# V2_1_1_AC_Power_Switch.net
KiCad netlist of a schematic drawn in EasyEDA Pro
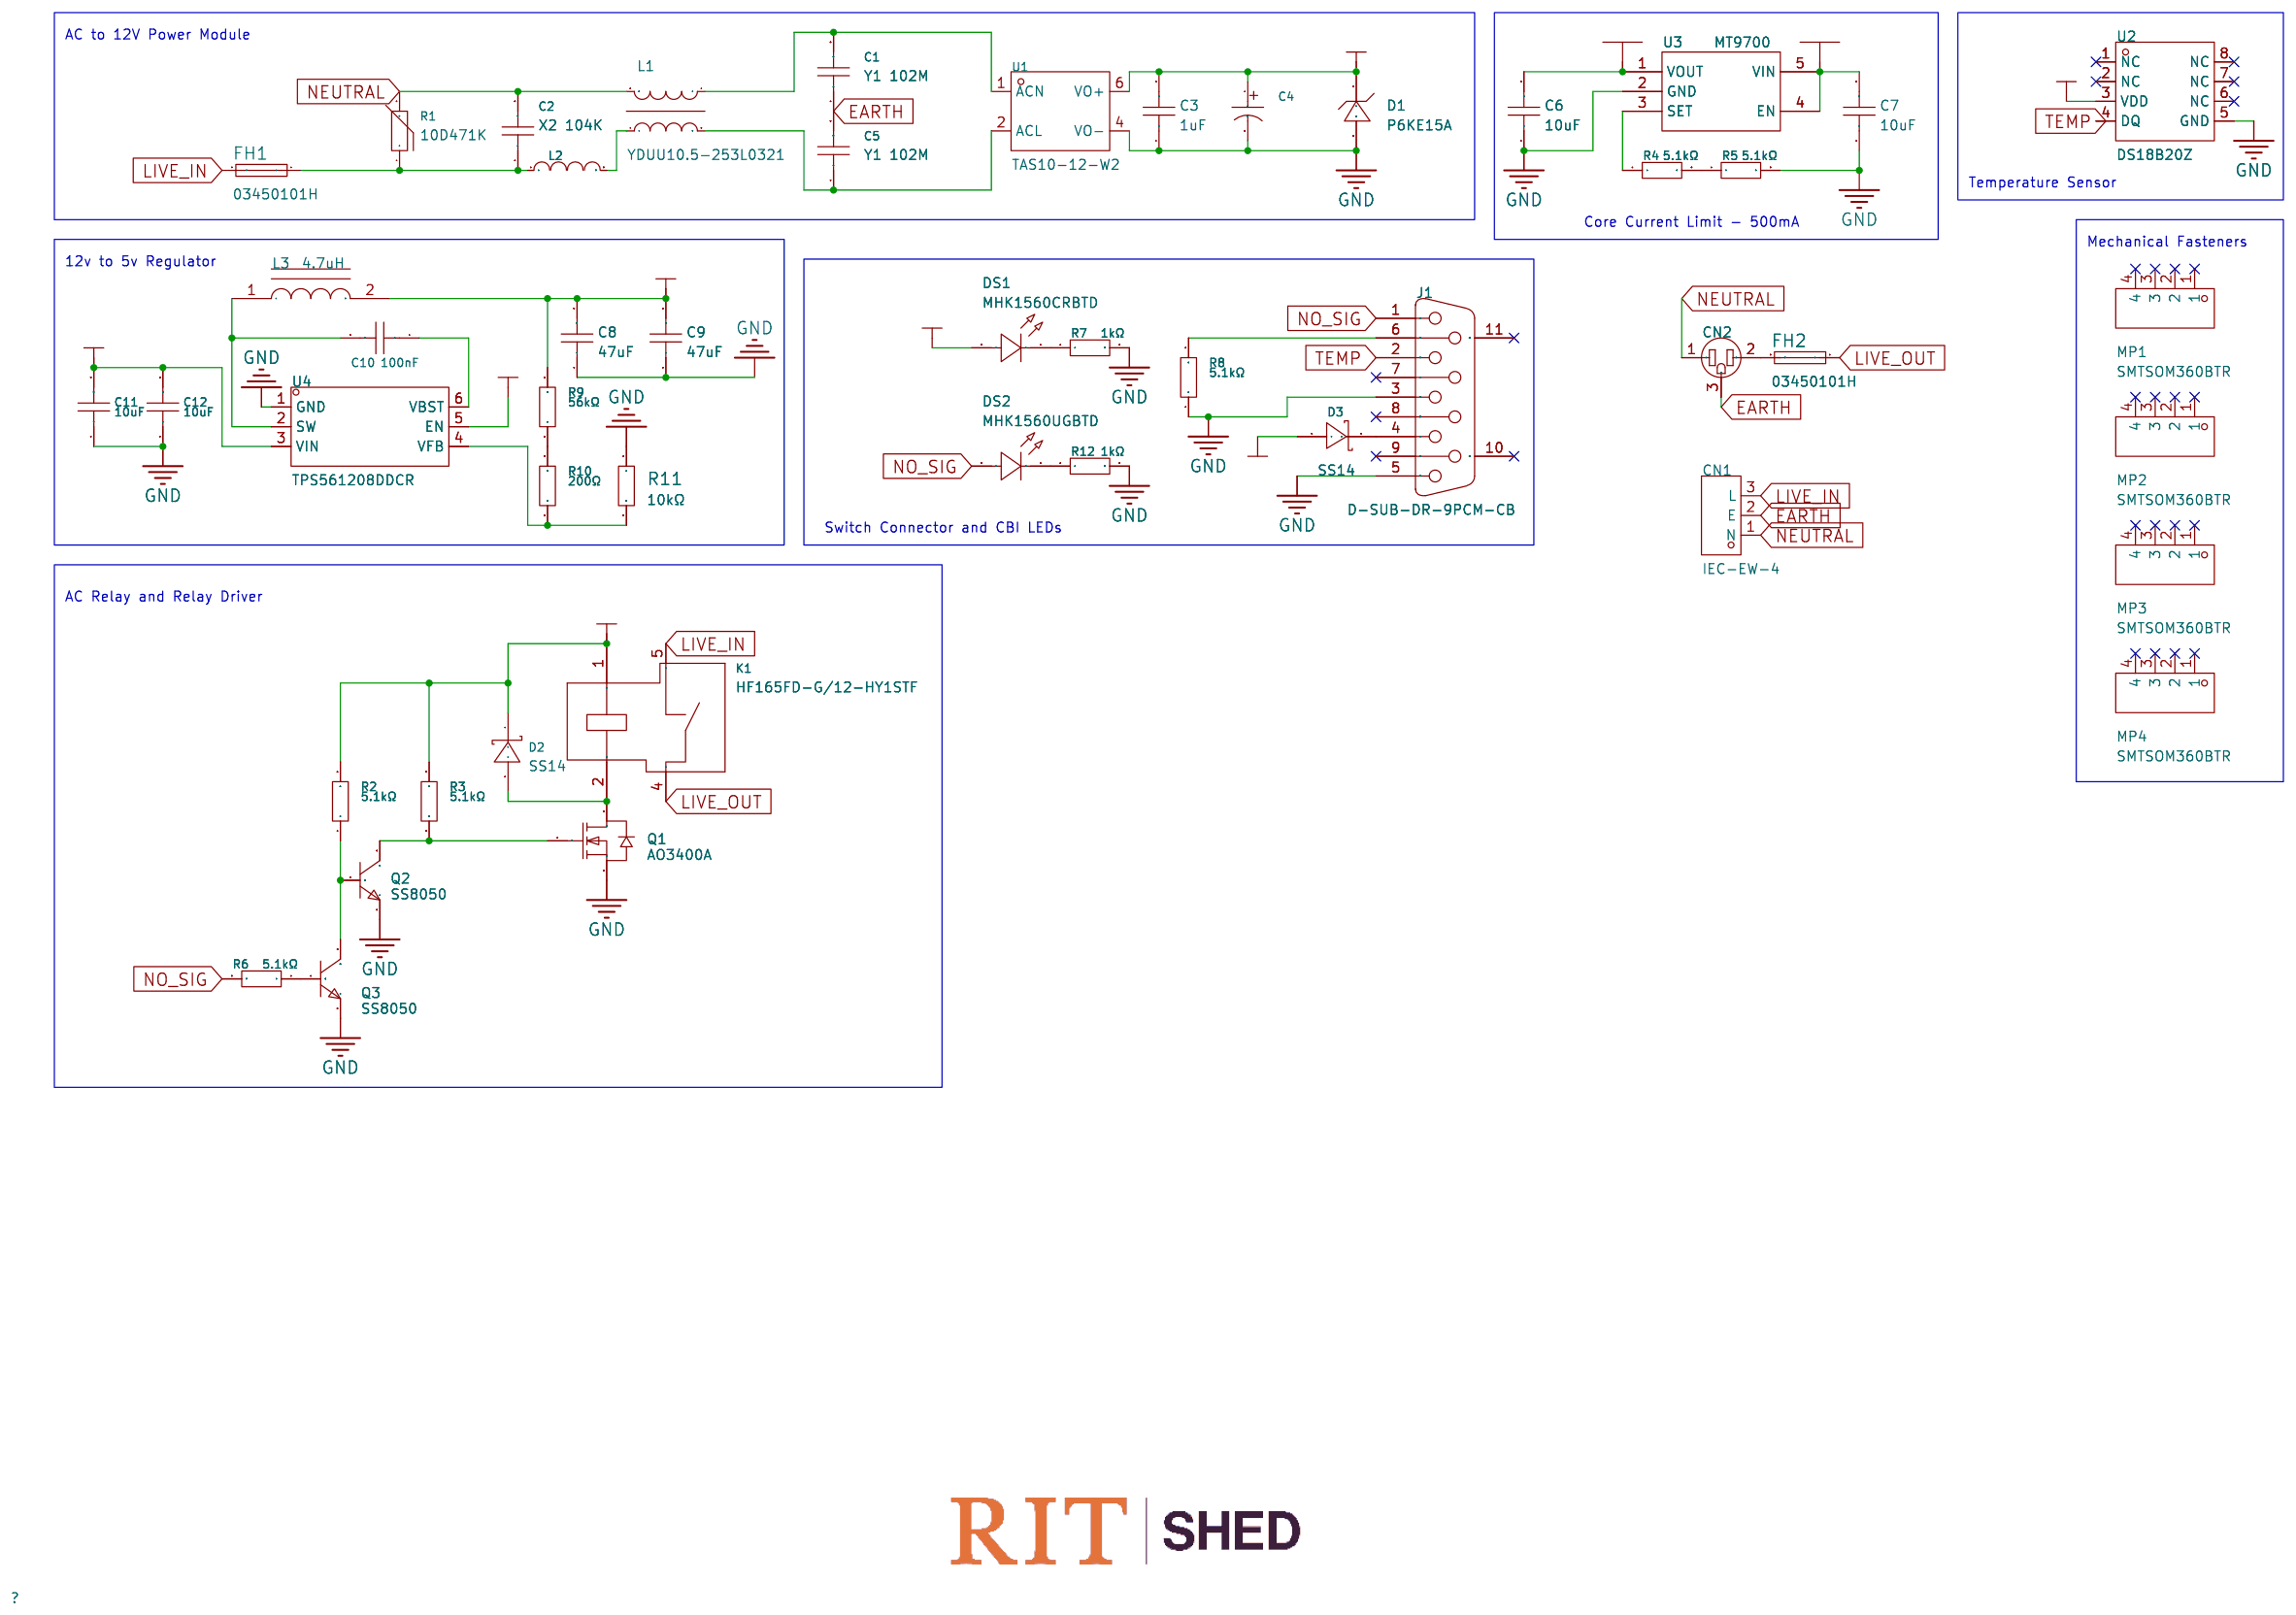
[diagram p0: schematic sheet]

(export (version "E")
  (design (tool "Eeschema 10.0.6"))
  (components
    (comp (ref "C1")
      (value "1nF")
      (footprint "easyedapro:CAP-TH_L8.5-W5.0-P10.00-D0.6")
      (fields
        (field (name "Manufacturer Part") "VY1102M31Y5UC63V0")
        (field (name "Manufacturer") "VISHAY(威世)")
      )
      (libsource (lib "easyedapro") (part "VY1102M31Y5UC63V0"))
    )
    (comp (ref "C2")
      (value "100nF")
      (footprint "easyedapro:CAP-TH_L10.0-W5.0-P7.50-D0.6")
      (fields (field (name "Manufacturer Part") "PX104K2C0702") (field (name "Manufacturer") "KYET(科雅)"))
      (libsource (lib "easyedapro") (part "PX104K2C0702"))
    )
    (comp (ref "C3")
      (value "1uF")
      (footprint "easyedapro:C1206")
      (fields
        (field (name "Manufacturer Part") "CL31B105KBHNNNE")
        (field (name "Manufacturer") "SAMSUNG(三星)")
      )
      (libsource (lib "easyedapro") (part "CL31B105KBHNNNE"))
    )
    (comp (ref "C4")
      (value "220uF")
      (footprint "easyedapro:CAP-TH_BD6.3-P2.50-D1.0-FD")
      (fields
        (field (name "Manufacturer Part") "KM227M025E11RR0VH2FP0")
        (field (name "Manufacturer") "CX(承兴)")
      )
      (libsource (lib "easyedapro") (part "220uF 25V_C12450"))
    )
    (comp (ref "C5")
      (value "1nF")
      (footprint "easyedapro:CAP-TH_L8.5-W5.0-P10.00-D0.6")
      (fields
        (field (name "Manufacturer Part") "VY1102M31Y5UC63V0")
        (field (name "Manufacturer") "VISHAY(威世)")
      )
      (libsource (lib "easyedapro") (part "VY1102M31Y5UC63V0"))
    )
    (comp (ref "C6")
      (value "10uF")
      (footprint "easyedapro:C0603")
      (fields
        (field (name "Manufacturer Part") "CL10A106MA8NRNC")
        (field (name "Manufacturer") "SAMSUNG(三星)")
      )
      (libsource (lib "easyedapro") (part "CL10A106MA8NRNC"))
    )
    (comp (ref "C7")
      (value "10uF")
      (footprint "easyedapro:C0603")
      (fields
        (field (name "Manufacturer Part") "CL10A106MA8NRNC")
        (field (name "Manufacturer") "SAMSUNG(三星)")
      )
      (libsource (lib "easyedapro") (part "CL10A106MA8NRNC"))
    )
    (comp (ref "C8")
      (value "47uF")
      (footprint "easyedapro:C1206")
      (fields
        (field (name "Manufacturer Part") "CL31A476MPHNNNE")
        (field (name "Manufacturer") "SAMSUNG(三星)")
      )
      (libsource (lib "easyedapro") (part "CL31A476MPHNNNE"))
    )
    (comp (ref "C9")
      (value "47uF")
      (footprint "easyedapro:C1206")
      (fields
        (field (name "Manufacturer Part") "CL31A476MPHNNNE")
        (field (name "Manufacturer") "SAMSUNG(三星)")
      )
      (libsource (lib "easyedapro") (part "CL31A476MPHNNNE"))
    )
    (comp (ref "C10")
      (value "100nF")
      (footprint "easyedapro:C0603")
      (fields
        (field (name "Manufacturer Part") "CC0603KRX7R9BB104")
        (field (name "Manufacturer") "YAGEO(国巨)")
      )
      (libsource (lib "easyedapro") (part "CC0603KRX7R9BB104"))
    )
    (comp (ref "C11")
      (value "10uF")
      (footprint "easyedapro:C0603")
      (fields
        (field (name "Manufacturer Part") "CL10A106MA8NRNC")
        (field (name "Manufacturer") "SAMSUNG(三星)")
      )
      (libsource (lib "easyedapro") (part "CL10A106MA8NRNC"))
    )
    (comp (ref "C12")
      (value "10uF")
      (footprint "easyedapro:C0603")
      (fields
        (field (name "Manufacturer Part") "CL10A106MA8NRNC")
        (field (name "Manufacturer") "SAMSUNG(三星)")
      )
      (libsource (lib "easyedapro") (part "CL10A106MA8NRNC"))
    )
    (comp (ref "CN1")
      (value "IEC-EW-4")
      (footprint "easyedapro:CONN-TH_IEC-EW-4")
      (fields (field (name "Manufacturer") "ADAM TECH"))
      (libsource (lib "easyedapro") (part "IEC-EW-4"))
    )
    (comp (ref "CN2")
      (value "~")
      (footprint "easyedapro:739W-X2/32")
      (libsource (lib "easyedapro") (part "739W-X2/32"))
    )
    (comp (ref "D1")
      (value "P6KE15A")
      (footprint "easyedapro:DO-15_BD3.1-L6.7-P10.70-D0.9-RD")
      (fields (field (name "Manufacturer") "PINGWEI(平伟)"))
      (libsource (lib "easyedapro") (part "P6KE15A_C432720"))
    )
    (comp (ref "D2")
      (value "SS14")
      (footprint "easyedapro:SMA_L4.2-W2.6-LS5.3-RD")
      (fields (field (name "Manufacturer") "MDD"))
      (libsource (lib "easyedapro") (part "SS14"))
    )
    (comp (ref "D3")
      (value "SS14")
      (footprint "easyedapro:SMA_L4.2-W2.6-LS5.3-RD")
      (fields (field (name "Manufacturer") "MDD"))
      (libsource (lib "easyedapro") (part "SS14"))
    )
    (comp (ref "DS1")
      (value "MHK1560CRBTD")
      (footprint "easyedapro:LED-TH_MHK1560UGBTD")
      (fields (field (name "Manufacturer") "MEIHUA(美华)"))
      (libsource (lib "easyedapro") (part "MHK1560CGBTD"))
    )
    (comp (ref "DS2")
      (value "MHK1560UGBTD")
      (footprint "easyedapro:LED-TH_MHK1560UGBTD")
      (fields (field (name "Manufacturer") "MEIHUA(美华)"))
      (libsource (lib "easyedapro") (part "MHK1560UGBTD"))
    )
    (comp (ref "FH1")
      (value "03450101H")
      (footprint "easyedapro:03450101H")
      (description "Fuseholder Type:- Fuse Type:- Fuse Size:-")
      (fields (field (name "Manufacturer") "Littelfuse(美国力特)"))
      (libsource (lib "easyedapro") (part "03450101H"))
    )
    (comp (ref "FH2")
      (value "03450101H")
      (footprint "easyedapro:03450101H")
      (description "Fuseholder Type:- Fuse Type:- Fuse Size:-")
      (fields (field (name "Manufacturer") "Littelfuse(美国力特)"))
      (libsource (lib "easyedapro") (part "03450101H"))
    )
    (comp (ref "J1")
      (value "D-SUB-DR-9PCM-CB")
      (footprint "easyedapro:DB9-TH_ID09S33E4GV00LF")
      (fields (field (name "Manufacturer") "XUNPU(讯普)"))
      (libsource (lib "easyedapro") (part "D-SUB-DR-9PCM-CB"))
    )
    (comp (ref "K1")
      (value "HF165FD-G/12-HY1STF")
      (footprint "easyedapro:RELAY-TH_HF165FD-G-12-HY1STF")
      (fields (field (name "Manufacturer") "HF(宏发)"))
      (libsource (lib "easyedapro") (part "HF165FD-G/12-HY1STF"))
    )
    (comp (ref "L1")
      (value "YDUU10.5-253L0321")
      (footprint "easyedapro:IND-TH_4P-L19.0-W17.0")
      (description "Number of Lines:2 Withstanding Voltage:1.5kV@AC Inductance @ Frequency:25mH@1KHz")
      (fields (field (name "Manufacturer") "YJYCOIN(益嘉源)"))
      (libsource (lib "easyedapro") (part "YDUU10.5-253L0321"))
    )
    (comp (ref "L2")
      (value "560uH")
      (footprint "easyedapro:IND-TH_BD9.0-P5.00-D0.7")
      (description "Inductance: Tolerance:±10% Tolerance:±10% Rated Current: DC Resistance (DCR): Type:工字电感")
      (fields (field (name "Manufacturer Part") "PK0810-561KB") (field (name "Manufacturer") "SXN(顺翔诺)"))
      (libsource (lib "easyedapro") (part "PK0810-561KB"))
    )
    (comp (ref "L3")
      (value "4.7uH")
      (footprint "easyedapro:IND-SMD_L4.4-W4.2")
      (fields (field (name "Manufacturer Part") "BCIHP0420SC-4R7M") (field (name "Manufacturer") "BC(台湾诚阳)"))
      (libsource (lib "easyedapro") (part "BCIHP0420SC-4R7M_C2921168"))
    )
    (comp (ref "MP1")
      (value "SMTSOM360BTR")
      (footprint "easyedapro:SMD_BD5.6-D4.1")
      (fields (field (name "Manufacturer") "YIYUAN(怡远)"))
      (libsource (lib "easyedapro") (part "SMTSOM360BTR"))
    )
    (comp (ref "MP2")
      (value "SMTSOM360BTR")
      (footprint "easyedapro:SMD_BD5.6-D4.1")
      (fields (field (name "Manufacturer") "YIYUAN(怡远)"))
      (libsource (lib "easyedapro") (part "SMTSOM360BTR"))
    )
    (comp (ref "MP3")
      (value "SMTSOM360BTR")
      (footprint "easyedapro:SMD_BD5.6-D4.1")
      (fields (field (name "Manufacturer") "YIYUAN(怡远)"))
      (libsource (lib "easyedapro") (part "SMTSOM360BTR"))
    )
    (comp (ref "MP4")
      (value "SMTSOM360BTR")
      (footprint "easyedapro:SMD_BD5.6-D4.1")
      (fields (field (name "Manufacturer") "YIYUAN(怡远)"))
      (libsource (lib "easyedapro") (part "SMTSOM360BTR"))
    )
    (comp (ref "Q1")
      (value "AO3400A")
      (footprint "easyedapro:SOT-23-3_L2.9-W1.3-P1.90-LS2.4-BR")
      (fields (field (name "Manufacturer") "AOS"))
      (libsource (lib "easyedapro") (part "AO3400A"))
    )
    (comp (ref "Q2")
      (value "SS8050")
      (footprint "easyedapro:SOT-23-3_L2.9-W1.3-P1.90-LS2.4-BR")
      (fields (field (name "Manufacturer") "CJ(江苏长电/长晶)"))
      (libsource (lib "easyedapro") (part "SS8050_C2150"))
    )
    (comp (ref "Q3")
      (value "SS8050")
      (footprint "easyedapro:SOT-23-3_L2.9-W1.3-P1.90-LS2.4-BR")
      (fields (field (name "Manufacturer") "CJ(江苏长电/长晶)"))
      (libsource (lib "easyedapro") (part "SS8050_C2150"))
    )
    (comp (ref "R1")
      (value "10D471K")
      (footprint "easyedapro:RES-TH_L12.5-W6.7-P7.50-D1.2")
      (fields (field (name "Manufacturer") "RUILON(瑞隆源)"))
      (libsource (lib "easyedapro") (part "10D471K-C8760"))
    )
    (comp (ref "R2")
      (value "5.1kΩ")
      (footprint "easyedapro:R0603")
      (fields
        (field (name "Manufacturer Part") "0603WAF5101T5E")
        (field (name "Manufacturer") "UNI-ROYAL(厚声)")
      )
      (libsource (lib "easyedapro") (part "0603WAF5101T5E"))
    )
    (comp (ref "R3")
      (value "5.1kΩ")
      (footprint "easyedapro:R0603")
      (fields
        (field (name "Manufacturer Part") "0603WAF5101T5E")
        (field (name "Manufacturer") "UNI-ROYAL(厚声)")
      )
      (libsource (lib "easyedapro") (part "0603WAF5101T5E"))
    )
    (comp (ref "R4")
      (value "5.1kΩ")
      (footprint "easyedapro:R0603")
      (fields
        (field (name "Manufacturer Part") "0603WAF5101T5E")
        (field (name "Manufacturer") "UNI-ROYAL(厚声)")
      )
      (libsource (lib "easyedapro") (part "0603WAF5101T5E"))
    )
    (comp (ref "R5")
      (value "5.1kΩ")
      (footprint "easyedapro:R0603")
      (fields
        (field (name "Manufacturer Part") "0603WAF5101T5E")
        (field (name "Manufacturer") "UNI-ROYAL(厚声)")
      )
      (libsource (lib "easyedapro") (part "0603WAF5101T5E"))
    )
    (comp (ref "R6")
      (value "5.1kΩ")
      (footprint "easyedapro:R0603")
      (fields
        (field (name "Manufacturer Part") "0603WAF5101T5E")
        (field (name "Manufacturer") "UNI-ROYAL(厚声)")
      )
      (libsource (lib "easyedapro") (part "0603WAF5101T5E"))
    )
    (comp (ref "R7")
      (value "1kΩ")
      (footprint "easyedapro:R0603")
      (fields
        (field (name "Manufacturer Part") "0603WAF1001T5E")
        (field (name "Manufacturer") "UNI-ROYAL(厚声)")
      )
      (libsource (lib "easyedapro") (part "0603WAF1001T5E"))
    )
    (comp (ref "R8")
      (value "5.1kΩ")
      (footprint "easyedapro:R0603")
      (fields
        (field (name "Manufacturer Part") "0603WAF5101T5E")
        (field (name "Manufacturer") "UNI-ROYAL(厚声)")
      )
      (libsource (lib "easyedapro") (part "0603WAF5101T5E"))
    )
    (comp (ref "R9")
      (value "56kΩ")
      (footprint "easyedapro:R0603")
      (fields
        (field (name "Manufacturer Part") "0603WAF5602T5E")
        (field (name "Manufacturer") "UNI-ROYAL(厚声)")
      )
      (libsource (lib "easyedapro") (part "0603WAF5602T5E"))
    )
    (comp (ref "R10")
      (value "200Ω")
      (footprint "easyedapro:R0603")
      (fields
        (field (name "Manufacturer Part") "0603WAF2000T5E")
        (field (name "Manufacturer") "UNI-ROYAL(厚声)")
      )
      (libsource (lib "easyedapro") (part "0603WAF2000T5E"))
    )
    (comp (ref "R11")
      (value "10kΩ")
      (footprint "easyedapro:R0603")
      (fields
        (field (name "Manufacturer Part") "0603WAF1002T5E")
        (field (name "Manufacturer") "UNI-ROYAL(厚声)")
      )
      (libsource (lib "easyedapro") (part "0603WAF1002T5E"))
    )
    (comp (ref "R12")
      (value "1kΩ")
      (footprint "easyedapro:R0603")
      (fields
        (field (name "Manufacturer Part") "0603WAF1001T5E")
        (field (name "Manufacturer") "UNI-ROYAL(厚声)")
      )
      (libsource (lib "easyedapro") (part "0603WAF1001T5E"))
    )
    (comp (ref "U1")
      (value "TAS10-12-W2")
      (footprint "easyedapro:PWRM-TH_TAS10-XX-W2")
      (fields (field (name "Manufacturer") "TDPOWER(腾达电源)"))
      (libsource (lib "easyedapro") (part "TAS10-12-W2"))
    )
    (comp (ref "U2")
      (value "DS18B20Z")
      (footprint "easyedapro:SOP-8_L4.9-W3.9-P1.27-LS6.0-BL")
      (description "Resolution:±0.4°C Resolution:±0.4°C Supply Voltage:2.5V~5.5V Supply Voltage:2.5V~5.5V")
      (fields (field (name "Manufacturer") "UMW(友台半导体)"))
      (libsource (lib "easyedapro") (part "DS18B20Z"))
    )
    (comp (ref "U3")
      (value "MT9700")
      (footprint "easyedapro:SOT-23-5_L3.0-W1.7-P0.95-LS2.8-BR")
      (fields (field (name "Manufacturer") "西安航天民芯"))
      (libsource (lib "easyedapro") (part "MT9700"))
    )
    (comp (ref "U4")
      (value "TPS561208DDCR")
      (footprint "easyedapro:TSOT-23-6_L2.9-W1.6-P0.95-LS2.8-BR")
      (fields (field (name "Manufacturer") "TI(德州仪器)"))
      (libsource (lib "easyedapro") (part "TPS561208DDCR"))
    )
  )
  (nets
    (net (code "1") (name "EARTH") (class "Default")
      (node (ref "C1") (pin "1") (pinfunction "1_1") (pintype "input"))
      (node (ref "C5") (pin "2") (pinfunction "2_2") (pintype "input"))
      (node (ref "CN1") (pin "2") (pinfunction "E_2") (pintype "unspecified"))
      (node (ref "CN2") (pin "3") (pinfunction "3_3") (pintype "unspecified"))
    )
    (net (code "2") (name "GND") (class "Default")
      (node (ref "C11") (pin "1") (pinfunction "1_1") (pintype "input"))
      (node (ref "C12") (pin "1") (pinfunction "1_1") (pintype "input"))
      (node (ref "C3") (pin "1") (pinfunction "1_1") (pintype "unspecified"))
      (node (ref "C4") (pin "2") (pinfunction "2_2") (pintype "input"))
      (node (ref "C6") (pin "1") (pinfunction "1_1") (pintype "input"))
      (node (ref "C7") (pin "1") (pinfunction "1_1") (pintype "input"))
      (node (ref "C8") (pin "1") (pinfunction "1_1") (pintype "unspecified"))
      (node (ref "C9") (pin "1") (pinfunction "1_1") (pintype "unspecified"))
      (node (ref "D1") (pin "2") (pinfunction "2_2") (pintype "unspecified"))
      (node (ref "J1") (pin "3") (pinfunction "3_3") (pintype "input"))
      (node (ref "J1") (pin "5") (pinfunction "5_5") (pintype "input"))
      (node (ref "Q1") (pin "2") (pinfunction "S_2") (pintype "unspecified"))
      (node (ref "Q2") (pin "2") (pinfunction "E_2") (pintype "unspecified"))
      (node (ref "Q3") (pin "2") (pinfunction "E_2") (pintype "unspecified"))
      (node (ref "R11") (pin "1") (pinfunction "1_1") (pintype "input"))
      (node (ref "R12") (pin "2") (pinfunction "2_2") (pintype "input"))
      (node (ref "R5") (pin "2") (pinfunction "2_2") (pintype "input"))
      (node (ref "R7") (pin "2") (pinfunction "2_2") (pintype "input"))
      (node (ref "R8") (pin "1") (pinfunction "1_1") (pintype "input"))
      (node (ref "U1") (pin "4") (pinfunction "VO-_4") (pintype "unspecified"))
      (node (ref "U2") (pin "5") (pinfunction "GND_5") (pintype "unspecified"))
      (node (ref "U3") (pin "2") (pinfunction "GND_2") (pintype "input"))
      (node (ref "U4") (pin "1") (pinfunction "GND_1") (pintype "unspecified"))
    )
    (net (code "3") (name "LIVE_IN") (class "Default")
      (node (ref "CN1") (pin "3") (pinfunction "L_3") (pintype "unspecified"))
      (node (ref "FH1") (pin "2") (pinfunction "2_2") (pintype "unspecified"))
      (node (ref "K1") (pin "5") (pinfunction "5_5") (pintype "input"))
    )
    (net (code "4") (name "LIVE_OUT") (class "Default")
      (node (ref "FH2") (pin "1") (pinfunction "1_1") (pintype "unspecified"))
      (node (ref "K1") (pin "4") (pinfunction "4_4") (pintype "input"))
    )
    (net (code "5") (name "NEUTRAL") (class "Default")
      (node (ref "C2") (pin "2") (pinfunction "2_2") (pintype "input"))
      (node (ref "CN1") (pin "1") (pinfunction "N_1") (pintype "unspecified"))
      (node (ref "CN2") (pin "1") (pinfunction "1_1") (pintype "unspecified"))
      (node (ref "L1") (pin "3") (pinfunction "3_3") (pintype "unspecified"))
      (node (ref "R1") (pin "2") (pinfunction "2_2") (pintype "input"))
    )
    (net (code "6") (name "NO_SIG") (class "Default")
      (node (ref "DS2") (pin "2") (pinfunction "A_2") (pintype "unspecified"))
      (node (ref "J1") (pin "1") (pinfunction "1_1") (pintype "input"))
      (node (ref "R6") (pin "2") (pinfunction "2_2") (pintype "input"))
    )
    (net (code "7") (name "Net-(C2-Pad1)") (class "Default")
      (node (ref "C2") (pin "1") (pinfunction "1_1") (pintype "input"))
      (node (ref "FH1") (pin "1") (pinfunction "1_1") (pintype "unspecified"))
      (node (ref "L2") (pin "1") (pinfunction "1_1") (pintype "input"))
      (node (ref "R1") (pin "1") (pinfunction "1_1") (pintype "input"))
    )
    (net (code "8") (name "Net-(CN2-Pad2)") (class "Default")
      (node (ref "CN2") (pin "2") (pinfunction "2_2") (pintype "unspecified"))
      (node (ref "FH2") (pin "2") (pinfunction "2_2") (pintype "unspecified"))
    )
    (net (code "9") (name "Net-(D2-A)") (class "Default")
      (node (ref "D2") (pin "2") (pinfunction "A_2") (pintype "unspecified"))
      (node (ref "K1") (pin "2") (pinfunction "2_2") (pintype "input"))
      (node (ref "Q1") (pin "3") (pinfunction "D_3") (pintype "unspecified"))
    )
    (net (code "10") (name "Net-(D3-K)") (class "Default")
      (node (ref "D3") (pin "1") (pinfunction "K_1") (pintype "unspecified"))
      (node (ref "J1") (pin "4") (pinfunction "4_4") (pintype "input"))
    )
    (net (code "11") (name "Net-(DS1-K)") (class "Default")
      (node (ref "DS1") (pin "1") (pinfunction "K_1") (pintype "unspecified"))
      (node (ref "R7") (pin "1") (pinfunction "1_1") (pintype "input"))
    )
    (net (code "12") (name "Net-(DS2-K)") (class "Default")
      (node (ref "DS2") (pin "1") (pinfunction "K_1") (pintype "unspecified"))
      (node (ref "R12") (pin "1") (pinfunction "1_1") (pintype "input"))
    )
    (net (code "13") (name "Net-(J1-Pad6)") (class "Default")
      (node (ref "J1") (pin "6") (pinfunction "6_6") (pintype "input"))
      (node (ref "R8") (pin "2") (pinfunction "2_2") (pintype "input"))
    )
    (net (code "14") (name "Net-(L1-Pad4)") (class "Default")
      (node (ref "L1") (pin "4") (pinfunction "4_4") (pintype "unspecified"))
      (node (ref "L2") (pin "2") (pinfunction "2_2") (pintype "input"))
    )
    (net (code "15") (name "Net-(Q1-G)") (class "Default")
      (node (ref "Q1") (pin "1") (pinfunction "G_1") (pintype "unspecified"))
      (node (ref "Q2") (pin "3") (pinfunction "C_3") (pintype "unspecified"))
      (node (ref "R3") (pin "1") (pinfunction "1_1") (pintype "input"))
    )
    (net (code "16") (name "Net-(Q2-B)") (class "Default")
      (node (ref "Q2") (pin "1") (pinfunction "B_1") (pintype "unspecified"))
      (node (ref "Q3") (pin "3") (pinfunction "C_3") (pintype "unspecified"))
      (node (ref "R2") (pin "1") (pinfunction "1_1") (pintype "input"))
    )
    (net (code "17") (name "Net-(Q3-B)") (class "Default")
      (node (ref "Q3") (pin "1") (pinfunction "B_1") (pintype "unspecified"))
      (node (ref "R6") (pin "1") (pinfunction "1_1") (pintype "input"))
    )
    (net (code "18") (name "Net-(R4-Pad2)") (class "Default")
      (node (ref "R4") (pin "2") (pinfunction "2_2") (pintype "input"))
      (node (ref "R5") (pin "1") (pinfunction "1_1") (pintype "input"))
    )
    (net (code "19") (name "Net-(R10-Pad2)") (class "Default")
      (node (ref "R10") (pin "2") (pinfunction "2_2") (pintype "input"))
      (node (ref "R9") (pin "1") (pinfunction "1_1") (pintype "input"))
    )
    (net (code "20") (name "Net-(U1-ACL)") (class "Default")
      (node (ref "C5") (pin "1") (pinfunction "1_1") (pintype "input"))
      (node (ref "L1") (pin "2") (pinfunction "2_2") (pintype "unspecified"))
      (node (ref "U1") (pin "2") (pinfunction "ACL_2") (pintype "unspecified"))
    )
    (net (code "21") (name "Net-(U1-ACN)") (class "Default")
      (node (ref "C1") (pin "2") (pinfunction "2_2") (pintype "input"))
      (node (ref "L1") (pin "1") (pinfunction "1_1") (pintype "unspecified"))
      (node (ref "U1") (pin "1") (pinfunction "ACN_1") (pintype "unspecified"))
    )
    (net (code "22") (name "Net-(U3-SET)") (class "Default")
      (node (ref "R4") (pin "1") (pinfunction "1_1") (pintype "input"))
      (node (ref "U3") (pin "3") (pinfunction "SET_3") (pintype "input"))
    )
    (net (code "23") (name "Net-(U4-SW)") (class "Default")
      (node (ref "C10") (pin "2") (pinfunction "2_2") (pintype "input"))
      (node (ref "L3") (pin "1") (pinfunction "1_1") (pintype "unspecified"))
      (node (ref "U4") (pin "2") (pinfunction "SW_2") (pintype "unspecified"))
    )
    (net (code "24") (name "Net-(U4-VBST)") (class "Default")
      (node (ref "C10") (pin "1") (pinfunction "1_1") (pintype "input"))
      (node (ref "U4") (pin "6") (pinfunction "VBST_6") (pintype "unspecified"))
    )
    (net (code "25") (name "Net-(U4-VFB)") (class "Default")
      (node (ref "R10") (pin "1") (pinfunction "1_1") (pintype "input"))
      (node (ref "R11") (pin "2") (pinfunction "2_2") (pintype "input"))
      (node (ref "U4") (pin "4") (pinfunction "VFB_4") (pintype "unspecified"))
    )
    (net (code "26") (name "TEMP") (class "Default")
      (node (ref "J1") (pin "2") (pinfunction "2_2") (pintype "input"))
      (node (ref "U2") (pin "4") (pinfunction "DQ_4") (pintype "unspecified"))
    )
    (net (code "27") (name "VIN") (class "Default")
      (node (ref "C7") (pin "2") (pinfunction "2_2") (pintype "input"))
      (node (ref "C8") (pin "2") (pinfunction "2_2") (pintype "unspecified"))
      (node (ref "C9") (pin "2") (pinfunction "2_2") (pintype "unspecified"))
      (node (ref "L3") (pin "2") (pinfunction "2_2") (pintype "unspecified"))
      (node (ref "R9") (pin "2") (pinfunction "2_2") (pintype "input"))
      (node (ref "U2") (pin "3") (pinfunction "VDD_3") (pintype "unspecified"))
      (node (ref "U3") (pin "4") (pinfunction "EN_4") (pintype "input"))
      (node (ref "U3") (pin "5") (pinfunction "VIN_5") (pintype "input"))
    )
    (net (code "28") (name "VRAW") (class "Default")
      (node (ref "C11") (pin "2") (pinfunction "2_2") (pintype "input"))
      (node (ref "C12") (pin "2") (pinfunction "2_2") (pintype "input"))
      (node (ref "C3") (pin "2") (pinfunction "2_2") (pintype "unspecified"))
      (node (ref "C4") (pin "1") (pinfunction "1_1") (pintype "input"))
      (node (ref "D1") (pin "1") (pinfunction "1_1") (pintype "unspecified"))
      (node (ref "D2") (pin "1") (pinfunction "K_1") (pintype "unspecified"))
      (node (ref "K1") (pin "1") (pinfunction "1_1") (pintype "input"))
      (node (ref "R2") (pin "2") (pinfunction "2_2") (pintype "input"))
      (node (ref "R3") (pin "2") (pinfunction "2_2") (pintype "input"))
      (node (ref "U1") (pin "6") (pinfunction "VO+_6") (pintype "unspecified"))
      (node (ref "U4") (pin "3") (pinfunction "VIN_3") (pintype "unspecified"))
      (node (ref "U4") (pin "5") (pinfunction "EN_5") (pintype "unspecified"))
    )
    (net (code "29") (name "VSW") (class "Default")
      (node (ref "C6") (pin "2") (pinfunction "2_2") (pintype "input"))
      (node (ref "D3") (pin "2") (pinfunction "A_2") (pintype "unspecified"))
      (node (ref "DS1") (pin "2") (pinfunction "A_2") (pintype "unspecified"))
      (node (ref "U3") (pin "1") (pinfunction "VOUT_1") (pintype "input"))
    )
    (net (code "30") (name "unconnected-(J1-MH1-Pad10)") (class "Default")
      (node (ref "J1") (pin "10") (pinfunction "MH1_10") (pintype "input+no_connect"))
    )
    (net (code "31") (name "unconnected-(J1-MH2-Pad11)") (class "Default")
      (node (ref "J1") (pin "11") (pinfunction "MH2_11") (pintype "input+no_connect"))
    )
    (net (code "32") (name "unconnected-(J1-Pad7)") (class "Default")
      (node (ref "J1") (pin "7") (pinfunction "7_7") (pintype "input+no_connect"))
    )
    (net (code "33") (name "unconnected-(J1-Pad8)") (class "Default")
      (node (ref "J1") (pin "8") (pinfunction "8_8") (pintype "input+no_connect"))
    )
    (net (code "34") (name "unconnected-(J1-Pad9)") (class "Default")
      (node (ref "J1") (pin "9") (pinfunction "9_9") (pintype "input+no_connect"))
    )
    (net (code "35") (name "unconnected-(MP1-Pad1)") (class "Default")
      (node (ref "MP1") (pin "1") (pinfunction "1_1") (pintype "unspecified+no_connect"))
    )
    (net (code "36") (name "unconnected-(MP1-Pad2)") (class "Default")
      (node (ref "MP1") (pin "2") (pinfunction "2_2") (pintype "unspecified+no_connect"))
    )
    (net (code "37") (name "unconnected-(MP1-Pad3)") (class "Default")
      (node (ref "MP1") (pin "3") (pinfunction "3_3") (pintype "unspecified+no_connect"))
    )
    (net (code "38") (name "unconnected-(MP1-Pad4)") (class "Default")
      (node (ref "MP1") (pin "4") (pinfunction "4_4") (pintype "unspecified+no_connect"))
    )
    (net (code "39") (name "unconnected-(MP2-Pad1)") (class "Default")
      (node (ref "MP2") (pin "1") (pinfunction "1_1") (pintype "unspecified+no_connect"))
    )
    (net (code "40") (name "unconnected-(MP2-Pad2)") (class "Default")
      (node (ref "MP2") (pin "2") (pinfunction "2_2") (pintype "unspecified+no_connect"))
    )
    (net (code "41") (name "unconnected-(MP2-Pad3)") (class "Default")
      (node (ref "MP2") (pin "3") (pinfunction "3_3") (pintype "unspecified+no_connect"))
    )
    (net (code "42") (name "unconnected-(MP2-Pad4)") (class "Default")
      (node (ref "MP2") (pin "4") (pinfunction "4_4") (pintype "unspecified+no_connect"))
    )
    (net (code "43") (name "unconnected-(MP3-Pad1)") (class "Default")
      (node (ref "MP3") (pin "1") (pinfunction "1_1") (pintype "unspecified+no_connect"))
    )
    (net (code "44") (name "unconnected-(MP3-Pad2)") (class "Default")
      (node (ref "MP3") (pin "2") (pinfunction "2_2") (pintype "unspecified+no_connect"))
    )
    (net (code "45") (name "unconnected-(MP3-Pad3)") (class "Default")
      (node (ref "MP3") (pin "3") (pinfunction "3_3") (pintype "unspecified+no_connect"))
    )
    (net (code "46") (name "unconnected-(MP3-Pad4)") (class "Default")
      (node (ref "MP3") (pin "4") (pinfunction "4_4") (pintype "unspecified+no_connect"))
    )
    (net (code "47") (name "unconnected-(MP4-Pad1)") (class "Default")
      (node (ref "MP4") (pin "1") (pinfunction "1_1") (pintype "unspecified+no_connect"))
    )
    (net (code "48") (name "unconnected-(MP4-Pad2)") (class "Default")
      (node (ref "MP4") (pin "2") (pinfunction "2_2") (pintype "unspecified+no_connect"))
    )
    (net (code "49") (name "unconnected-(MP4-Pad3)") (class "Default")
      (node (ref "MP4") (pin "3") (pinfunction "3_3") (pintype "unspecified+no_connect"))
    )
    (net (code "50") (name "unconnected-(MP4-Pad4)") (class "Default")
      (node (ref "MP4") (pin "4") (pinfunction "4_4") (pintype "unspecified+no_connect"))
    )
    (net (code "51") (name "unconnected-(U2-NC-Pad1)") (class "Default")
      (node (ref "U2") (pin "1") (pinfunction "NC_1") (pintype "unspecified+no_connect"))
    )
    (net (code "52") (name "unconnected-(U2-NC-Pad2)") (class "Default")
      (node (ref "U2") (pin "2") (pinfunction "NC_2") (pintype "unspecified+no_connect"))
    )
    (net (code "53") (name "unconnected-(U2-NC-Pad6)") (class "Default")
      (node (ref "U2") (pin "6") (pinfunction "NC_6") (pintype "unspecified+no_connect"))
    )
    (net (code "54") (name "unconnected-(U2-NC-Pad7)") (class "Default")
      (node (ref "U2") (pin "7") (pinfunction "NC_7") (pintype "unspecified+no_connect"))
    )
    (net (code "55") (name "unconnected-(U2-NC-Pad8)") (class "Default")
      (node (ref "U2") (pin "8") (pinfunction "NC_8") (pintype "unspecified+no_connect"))
    )
  )
)
